# ESP-12MOD.net
KiCad netlist of a schematic drawn in Altium Designer
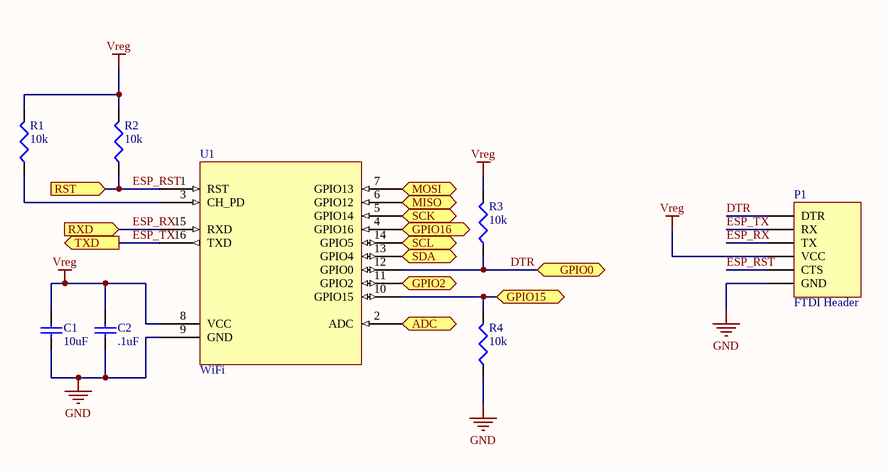
[diagram p0: ESP-12MOD.SchDoc]

(export (version "E")
  (design (tool "Eeschema 10.0.6"))
  (components
    (comp (ref "C1")
      (value "10uF")
      (footprint "1608[0603]")
      (fields (field (name "Comment") "Cap") (field (name "PUBLISHER") "Altium Limited"))
      (libsource (lib "Miscellaneous Devices") (part "Cap Semi"))
    )
    (comp (ref "C2")
      (value ".1uF")
      (footprint "1608[0603]")
      (fields (field (name "Comment") "Cap") (field (name "PUBLISHER") "Altium Limited"))
      (libsource (lib "Miscellaneous Devices") (part "Cap Semi"))
    )
    (comp (ref "P1")
      (value "FTDI Header")
      (footprint "HDR1X6")
      (description "Header, 6-Pin")
      (fields (field (name "PUBLISHER") "Altium Limited"))
      (libsource (lib "Miscellaneous Connectors") (part "FTDI Header"))
    )
    (comp (ref "R1")
      (value "10k")
      (footprint "J1-0603")
      (description "Resistor")
      (fields (field (name "Comment") "Res3") (field (name "PUBLISHER") "Altium Limited"))
      (libsource (lib "Miscellaneous Devices") (part "Res3"))
    )
    (comp (ref "R2")
      (value "10k")
      (footprint "J1-0603")
      (description "Resistor")
      (fields (field (name "Comment") "Res3") (field (name "PUBLISHER") "Altium Limited"))
      (libsource (lib "Miscellaneous Devices") (part "Res3"))
    )
    (comp (ref "R3")
      (value "10k")
      (footprint "J1-0603")
      (description "Resistor")
      (fields (field (name "Comment") "Res3") (field (name "PUBLISHER") "Altium Limited"))
      (libsource (lib "Miscellaneous Devices") (part "Res3"))
    )
    (comp (ref "R4")
      (value "10k")
      (footprint "J1-0603")
      (description "Resistor")
      (fields (field (name "Comment") "Res3") (field (name "PUBLISHER") "Altium Limited"))
      (libsource (lib "Miscellaneous Devices") (part "Res3"))
    )
    (comp (ref "U1")
      (value "WiFi")
      (footprint "ESP8266ShieldedSMD")
      (libsource (lib "Miscellaneous Devices") (part "ESP8266-Shielded"))
    )
  )
  (nets
    (net (code "1") (name "/ADC") (class "Default")
      (node (ref "U1") (pin "2") (pinfunction "ADC_2") (pintype "input"))
    )
    (net (code "2") (name "/DTR") (class "Default")
      (node (ref "P1") (pin "1") (pinfunction "DTR_1") (pintype "passive"))
      (node (ref "R3") (pin "1") (pinfunction "1_1") (pintype "passive"))
      (node (ref "U1") (pin "12") (pinfunction "GPIO0_12") (pintype "bidirectional"))
    )
    (net (code "3") (name "/ESP_RST") (class "Default")
      (node (ref "P1") (pin "5") (pinfunction "CTS_5") (pintype "passive"))
      (node (ref "R2") (pin "1") (pinfunction "1_1") (pintype "passive"))
      (node (ref "U1") (pin "1") (pinfunction "RST_1") (pintype "input"))
    )
    (net (code "4") (name "/ESP_RX") (class "Default")
      (node (ref "P1") (pin "3") (pinfunction "TX_3") (pintype "passive"))
      (node (ref "U1") (pin "15") (pinfunction "RXD_15") (pintype "input"))
    )
    (net (code "5") (name "/ESP_TX") (class "Default")
      (node (ref "P1") (pin "2") (pinfunction "RX_2") (pintype "passive"))
      (node (ref "U1") (pin "16") (pinfunction "TXD_16") (pintype "output"))
    )
    (net (code "6") (name "/GPIO2") (class "Default")
      (node (ref "U1") (pin "11") (pinfunction "GPIO2_11") (pintype "bidirectional"))
    )
    (net (code "7") (name "/GPIO15") (class "Default")
      (node (ref "R4") (pin "2") (pinfunction "2_2") (pintype "passive"))
      (node (ref "U1") (pin "10") (pinfunction "GPIO15_10") (pintype "bidirectional"))
    )
    (net (code "8") (name "/GPIO16") (class "Default")
      (node (ref "U1") (pin "4") (pinfunction "GPIO16_4") (pintype "input"))
    )
    (net (code "9") (name "/MISO") (class "Default")
      (node (ref "U1") (pin "6") (pinfunction "GPIO12_6") (pintype "input"))
    )
    (net (code "10") (name "/MOSI") (class "Default")
      (node (ref "U1") (pin "7") (pinfunction "GPIO13_7") (pintype "input"))
    )
    (net (code "11") (name "/SCK") (class "Default")
      (node (ref "U1") (pin "5") (pinfunction "GPIO14_5") (pintype "input"))
    )
    (net (code "12") (name "/SCL") (class "Default")
      (node (ref "U1") (pin "14") (pinfunction "GPIO5_14") (pintype "bidirectional"))
    )
    (net (code "13") (name "/SDA") (class "Default")
      (node (ref "U1") (pin "13") (pinfunction "GPIO4_13") (pintype "bidirectional"))
    )
    (net (code "14") (name "GND") (class "Default")
      (node (ref "C1") (pin "1") (pinfunction "1_1") (pintype "passive"))
      (node (ref "C2") (pin "1") (pinfunction "1_1") (pintype "passive"))
      (node (ref "P1") (pin "6") (pinfunction "GND_6") (pintype "passive"))
      (node (ref "R4") (pin "1") (pinfunction "1_1") (pintype "passive"))
      (node (ref "U1") (pin "9") (pinfunction "GND_9") (pintype "power_in"))
    )
    (net (code "15") (name "Net-(U1-CH_PD)") (class "Default")
      (node (ref "R1") (pin "1") (pinfunction "1_1") (pintype "passive"))
      (node (ref "U1") (pin "3") (pinfunction "CH_PD_3") (pintype "input"))
    )
    (net (code "16") (name "Vreg") (class "Default")
      (node (ref "C1") (pin "2") (pinfunction "2_2") (pintype "passive"))
      (node (ref "C2") (pin "2") (pinfunction "2_2") (pintype "passive"))
      (node (ref "P1") (pin "4") (pinfunction "VCC_4") (pintype "passive"))
      (node (ref "R1") (pin "2") (pinfunction "2_2") (pintype "passive"))
      (node (ref "R2") (pin "2") (pinfunction "2_2") (pintype "passive"))
      (node (ref "R3") (pin "2") (pinfunction "2_2") (pintype "passive"))
      (node (ref "U1") (pin "8") (pinfunction "VCC_8") (pintype "power_in"))
    )
  )
)
